# high_voltage_control.net
KiCad netlist of a schematic drawn in Altium Designer
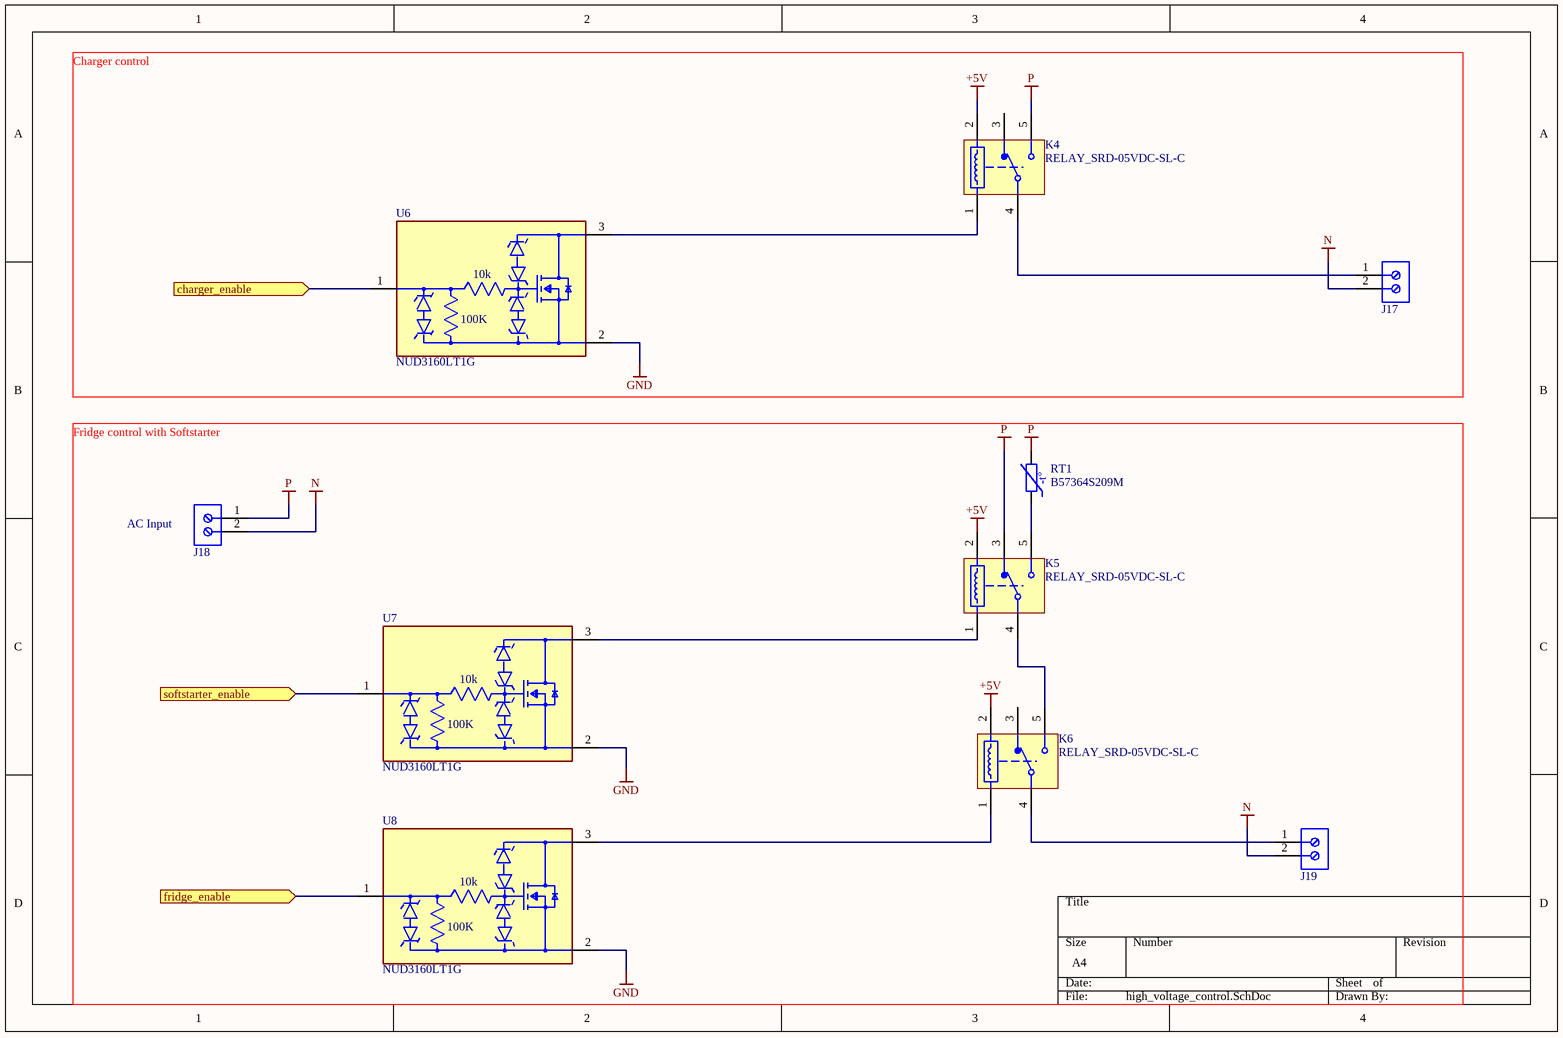
[diagram p0: high_voltage_control.SchDoc]

(export (version "E")
  (design (tool "Eeschema 10.0.6"))
  (components
    (comp (ref "J17")
      (value "282836-2")
      (footprint "TECO-282836-2_V")
      (description "Female Header, Pitch 5 mm, 1 x 2 Position, Height 10 mm, Tail Length 3.5 mm, Rohs, Bulk")
      (fields (field (name "VOLTAGE") "300V") (field (name "MANUFACTURER") "TE Connectivity"))
      (libsource (lib "Altium Content Vault") (part "CN-1P-F-TB2"))
    )
    (comp (ref "J18")
      (value "282836-2")
      (footprint "TECO-282836-2_V")
      (description "Female Header, Pitch 5 mm, 1 x 2 Position, Height 10 mm, Tail Length 3.5 mm, Rohs, Bulk")
      (fields (field (name "VOLTAGE") "300V") (field (name "MANUFACTURER") "TE Connectivity"))
      (libsource (lib "Altium Content Vault") (part "CN-1P-F-TB2"))
    )
    (comp (ref "J19")
      (value "282836-2")
      (footprint "TECO-282836-2_V")
      (description "Female Header, Pitch 5 mm, 1 x 2 Position, Height 10 mm, Tail Length 3.5 mm, Rohs, Bulk")
      (fields (field (name "VOLTAGE") "300V") (field (name "MANUFACTURER") "TE Connectivity"))
      (libsource (lib "Altium Content Vault") (part "CN-1P-F-TB2"))
    )
    (comp (ref "K4")
      (value "RELAY_SRD-05VDC-SL-C")
      (footprint "SRD-05-VDC-SL-C")
      (description "5VDC SPDT Relay")
      (libsource (lib "integrated_library") (part "RELAY_SRD-05VDC-SL-C"))
    )
    (comp (ref "K5")
      (value "RELAY_SRD-05VDC-SL-C")
      (footprint "SRD-05-VDC-SL-C")
      (description "5VDC SPDT Relay")
      (libsource (lib "integrated_library") (part "RELAY_SRD-05VDC-SL-C"))
    )
    (comp (ref "K6")
      (value "RELAY_SRD-05VDC-SL-C")
      (footprint "SRD-05-VDC-SL-C")
      (description "5VDC SPDT Relay")
      (libsource (lib "integrated_library") (part "RELAY_SRD-05VDC-SL-C"))
    )
    (comp (ref "RT1")
      (value "B57364S209M")
      (footprint "TDK-B57364")
      (description "Inrush Current Limiter, 2 Ohm, -55 to 170 degC, 2-Pin THD, RoHS, Bulk")
      (fields (field (name "MANUFACTURER") "TDK"))
      (libsource (lib "Altium Content Vault") (part "RES-NTC-2"))
    )
    (comp (ref "U6")
      (value "NUD3160LT1G")
      (footprint "FP-318-08-MFG")
      (description "IC INDCT LOAD DRVR INDUST SOT23")
      (fields
        (field (name "OCTOPART") "https://octopart.com/nud3160lt1g-on+semiconductor-470723")
        (field (name "MANUFACTURER") "ON Semiconductor")
      )
      (libsource (lib "Altium Content Vault") (part "3565ae214b0a124fee97343a38643ca"))
    )
    (comp (ref "U7")
      (value "NUD3160LT1G")
      (footprint "FP-318-08-MFG")
      (description "IC INDCT LOAD DRVR INDUST SOT23")
      (fields
        (field (name "OCTOPART") "https://octopart.com/nud3160lt1g-on+semiconductor-470723")
        (field (name "MANUFACTURER") "ON Semiconductor")
      )
      (libsource (lib "Altium Content Vault") (part "3565ae214b0a124fee97343a38643ca"))
    )
    (comp (ref "U8")
      (value "NUD3160LT1G")
      (footprint "FP-318-08-MFG")
      (description "IC INDCT LOAD DRVR INDUST SOT23")
      (fields
        (field (name "OCTOPART") "https://octopart.com/nud3160lt1g-on+semiconductor-470723")
        (field (name "MANUFACTURER") "ON Semiconductor")
      )
      (libsource (lib "Altium Content Vault") (part "3565ae214b0a124fee97343a38643ca"))
    )
  )
  (nets
    (net (code "1") (name "+5V") (class "Default")
      (node (ref "K4") (pin "2") (pinfunction "2_2") (pintype "passive"))
      (node (ref "K5") (pin "2") (pinfunction "2_2") (pintype "passive"))
      (node (ref "K6") (pin "2") (pinfunction "2_2") (pintype "passive"))
    )
    (net (code "2") (name "/charger_enable") (class "Default")
      (node (ref "U6") (pin "1") (pinfunction "Gate_1") (pintype "passive"))
    )
    (net (code "3") (name "/fridge_enable") (class "Default")
      (node (ref "U8") (pin "1") (pinfunction "Gate_1") (pintype "passive"))
    )
    (net (code "4") (name "/softstarter_enable") (class "Default")
      (node (ref "U7") (pin "1") (pinfunction "Gate_1") (pintype "passive"))
    )
    (net (code "5") (name "GND") (class "Default")
      (node (ref "U6") (pin "2") (pinfunction "Source_2") (pintype "passive"))
      (node (ref "U7") (pin "2") (pinfunction "Source_2") (pintype "passive"))
      (node (ref "U8") (pin "2") (pinfunction "Source_2") (pintype "passive"))
    )
    (net (code "6") (name "N") (class "Default")
      (node (ref "J17") (pin "2") (pinfunction "2_2") (pintype "passive"))
      (node (ref "J18") (pin "2") (pinfunction "2_2") (pintype "passive"))
      (node (ref "J19") (pin "2") (pinfunction "2_2") (pintype "passive"))
    )
    (net (code "7") (name "Net-(K4-COM)") (class "Default")
      (node (ref "J17") (pin "1") (pinfunction "1_1") (pintype "passive"))
      (node (ref "K4") (pin "4") (pinfunction "COM_4") (pintype "passive"))
    )
    (net (code "8") (name "Net-(K5-COM)") (class "Default")
      (node (ref "K5") (pin "4") (pinfunction "COM_4") (pintype "passive"))
      (node (ref "K6") (pin "5") (pinfunction "NO_5") (pintype "passive"))
    )
    (net (code "9") (name "Net-(K5-NO)") (class "Default")
      (node (ref "K5") (pin "5") (pinfunction "NO_5") (pintype "passive"))
      (node (ref "RT1") (pin "2") (pinfunction "2_2") (pintype "passive"))
    )
    (net (code "10") (name "Net-(K6-COM)") (class "Default")
      (node (ref "J19") (pin "1") (pinfunction "1_1") (pintype "passive"))
      (node (ref "K6") (pin "4") (pinfunction "COM_4") (pintype "passive"))
    )
    (net (code "11") (name "Net-(U6-Drain)") (class "Default")
      (node (ref "K4") (pin "1") (pinfunction "1_1") (pintype "passive"))
      (node (ref "U6") (pin "3") (pinfunction "Drain_3") (pintype "passive"))
    )
    (net (code "12") (name "Net-(U7-Drain)") (class "Default")
      (node (ref "K5") (pin "1") (pinfunction "1_1") (pintype "passive"))
      (node (ref "U7") (pin "3") (pinfunction "Drain_3") (pintype "passive"))
    )
    (net (code "13") (name "Net-(U8-Drain)") (class "Default")
      (node (ref "K6") (pin "1") (pinfunction "1_1") (pintype "passive"))
      (node (ref "U8") (pin "3") (pinfunction "Drain_3") (pintype "passive"))
    )
    (net (code "14") (name "P") (class "Default")
      (node (ref "J18") (pin "1") (pinfunction "1_1") (pintype "passive"))
      (node (ref "K4") (pin "5") (pinfunction "NO_5") (pintype "passive"))
      (node (ref "K5") (pin "3") (pinfunction "NC_3") (pintype "passive"))
      (node (ref "RT1") (pin "1") (pinfunction "1_1") (pintype "passive"))
    )
    (net (code "15") (name "unconnected-(K4-NC-Pad3)") (class "Default")
      (node (ref "K4") (pin "3") (pinfunction "NC_3") (pintype "passive"))
    )
    (net (code "16") (name "unconnected-(K6-NC-Pad3)") (class "Default")
      (node (ref "K6") (pin "3") (pinfunction "NC_3") (pintype "passive"))
    )
  )
)
